# IOT_GRN_MAIN_V1_0_A_-_ESP32.net
KiCad netlist of a schematic drawn in Altium Designer
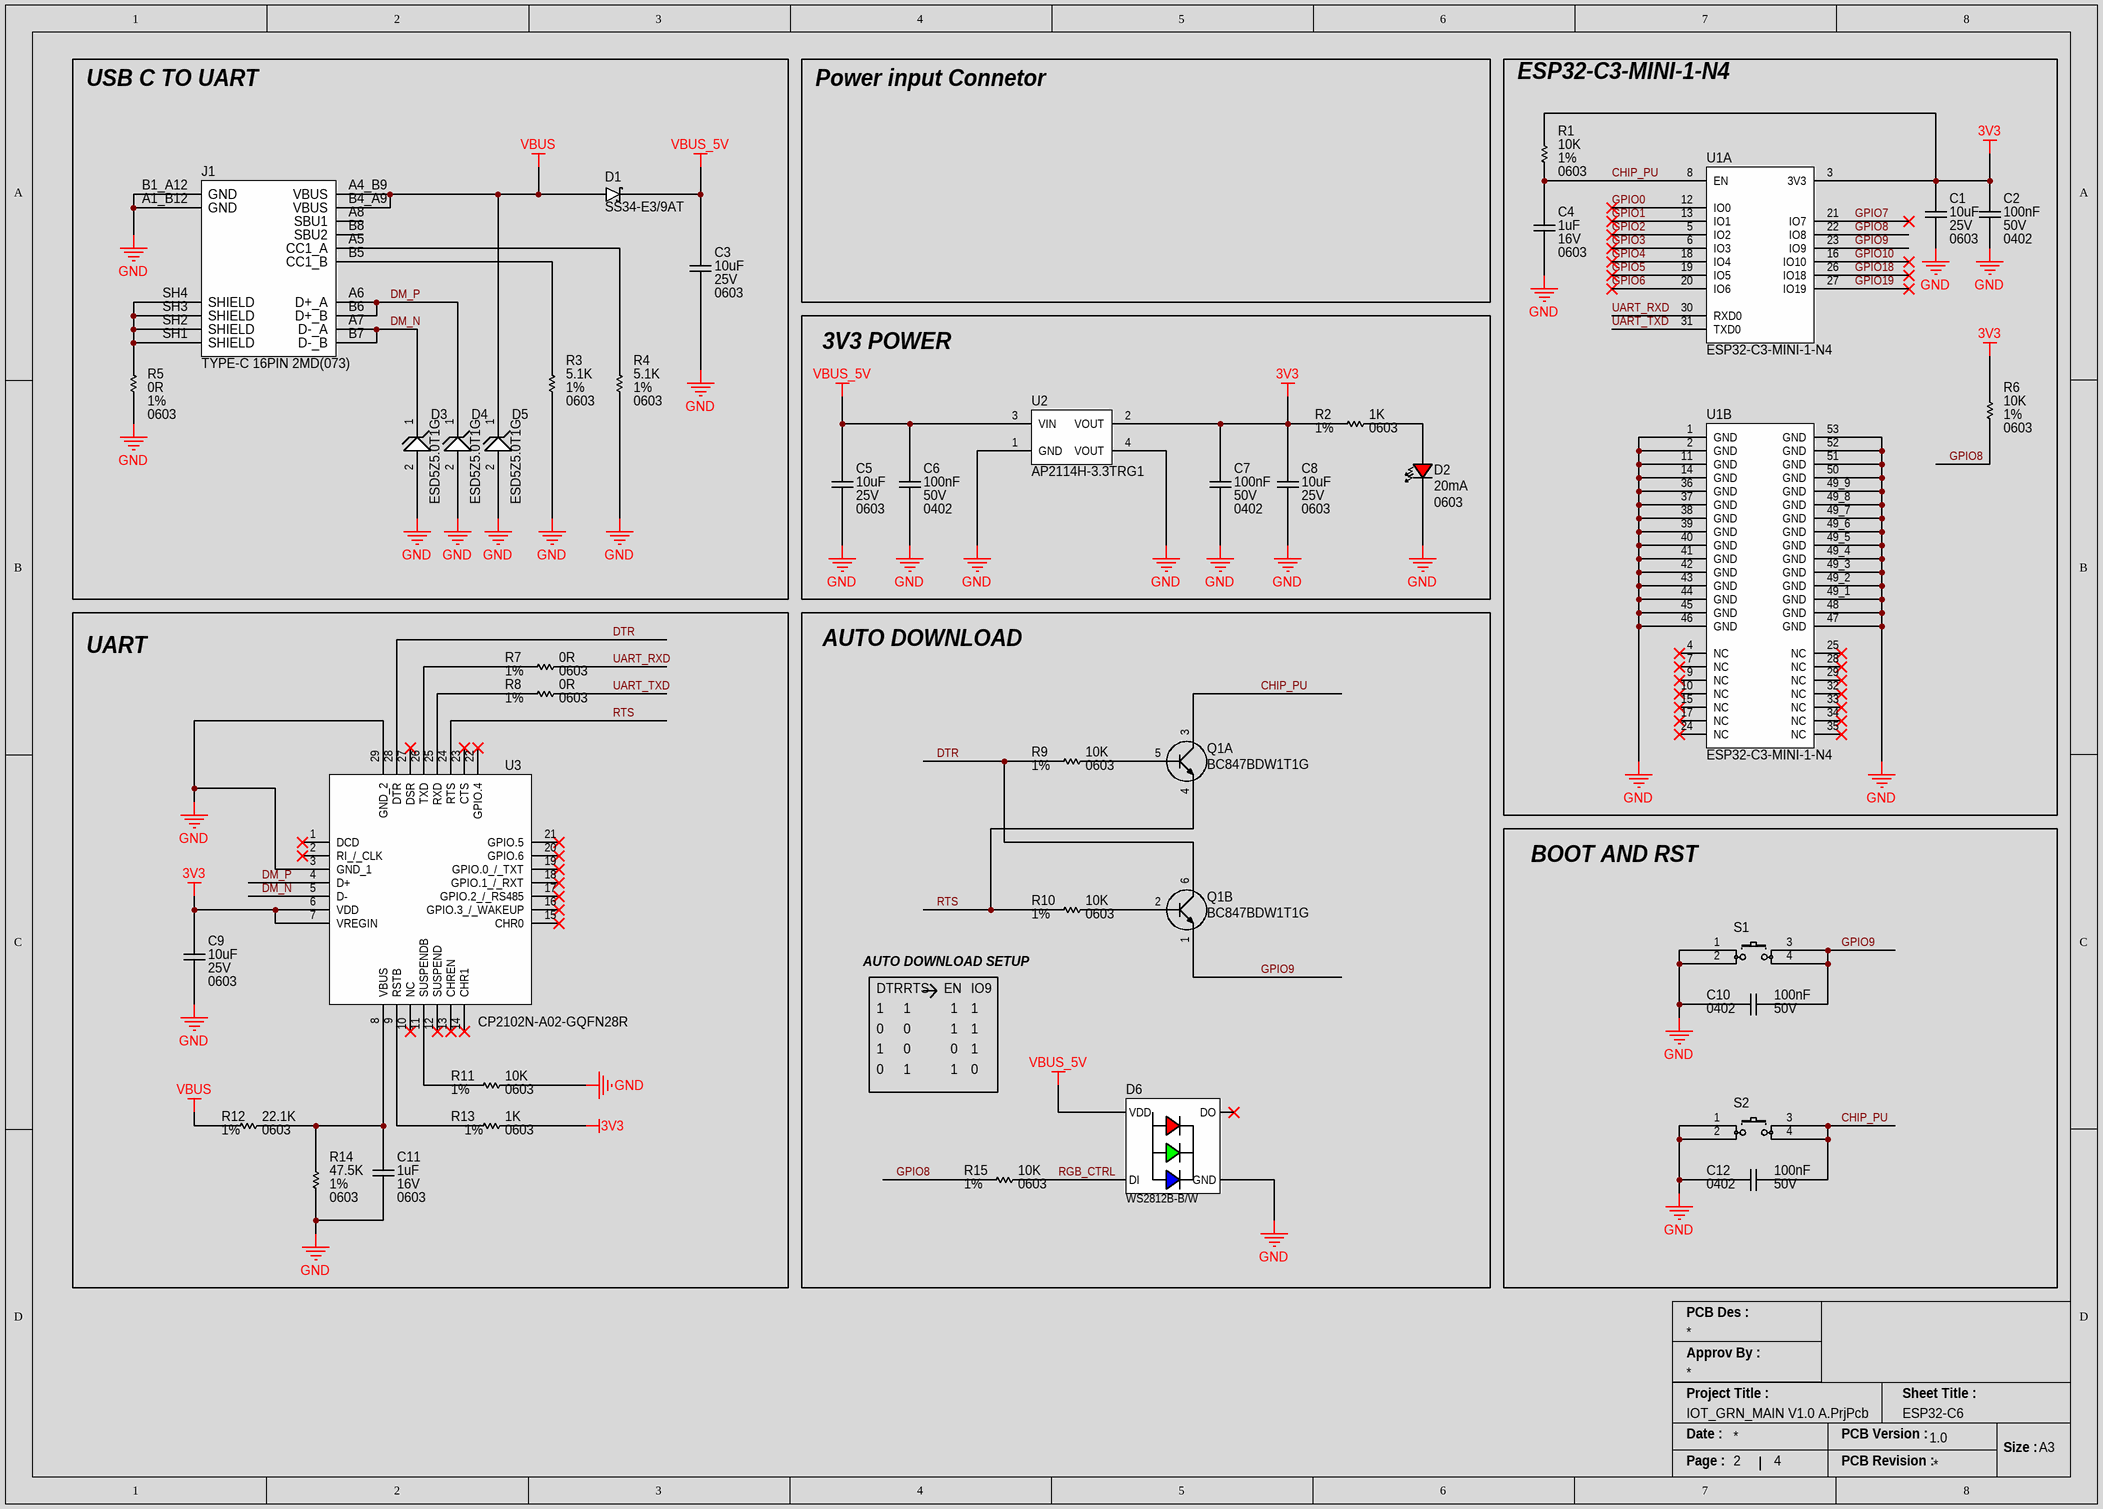
[diagram p0: IOT_GRN_MAIN V1.0 A - ESP32.SchDoc]

(export (version "E")
  (design (tool "Eeschema 10.0.6"))
  (components
    (comp (ref "C1")
      (value "GRM188R61E106MA73D")
      (footprint "CAP_0603_CAPC1608X08N")
      (description "Multilayer Ceramic Capacitor, 10 uF, 25 V, ± 20%, X5R, 0603 [1608 Metric]")
      (fields
        (field (name "MANUFACTURER") "Murata")
        (field (name "TOLERANCE") "20%")
        (field (name "CASE/PACKAGE") "0603")
        (field (name "CAPACITANCE") "10uF")
        (field (name "VOLTAGE RATING") "25V")
      )
      (libsource (lib "Electronic Devices_LIB") (part "CAP_10UF_25V_X5R_0603"))
    )
    (comp (ref "C2")
      (value "GRM155R71H104KE14D")
      (footprint "CAP_0402_CAPC1005X05N")
      (description "Multilayer Ceramic Capacitor, 0.1 uF, 16 V, ± 10%, X7R, 0402 [1005 Metric]")
      (fields
        (field (name "MANUFACTURER") "Murata")
        (field (name "TOLERANCE") "10%")
        (field (name "VOLTAGE RATING") "50V")
        (field (name "CAPACITANCE") "100nF")
        (field (name "CASE/PACKAGE") "0402")
      )
      (libsource (lib "Electronic Devices_LIB") (part "CAP_100NF_50V_X7R_0402"))
    )
    (comp (ref "C3")
      (value "GRM188R61E106MA73D")
      (footprint "CAP_0603_CAPC1608X08N")
      (description "Multilayer Ceramic Capacitor, 10 uF, 25 V, ± 20%, X5R, 0603 [1608 Metric]")
      (fields
        (field (name "MANUFACTURER") "Murata")
        (field (name "TOLERANCE") "20%")
        (field (name "CASE/PACKAGE") "0603")
        (field (name "CAPACITANCE") "10uF")
        (field (name "VOLTAGE RATING") "25V")
      )
      (libsource (lib "Electronic Devices_LIB") (part "CAP_10UF_25V_X5R_0603"))
    )
    (comp (ref "C4")
      (value "CL10A105KO8NNNC")
      (footprint "CAP_0603_CAPC1608X08N")
      (description "CAP CER 1UF 16V X5R 0603")
      (fields
        (field (name "MANUFACTURER") "Samsung")
        (field (name "TOLERANCE") "10%")
        (field (name "VOLTAGE RATING") "16V")
        (field (name "CAPACITANCE") "1uF")
        (field (name "CASE/PACKAGE") "0603")
      )
      (libsource (lib "Electronic Devices_LIB") (part "CAP_1UF_16V_X5R_0603"))
    )
    (comp (ref "C5")
      (value "GRM188R61E106MA73D")
      (footprint "CAP_0603_CAPC1608X08N")
      (description "Multilayer Ceramic Capacitor, 10 uF, 25 V, ± 20%, X5R, 0603 [1608 Metric]")
      (fields
        (field (name "MANUFACTURER") "Murata")
        (field (name "TOLERANCE") "20%")
        (field (name "CASE/PACKAGE") "0603")
        (field (name "CAPACITANCE") "10uF")
        (field (name "VOLTAGE RATING") "25V")
      )
      (libsource (lib "Electronic Devices_LIB") (part "CAP_10UF_25V_X5R_0603"))
    )
    (comp (ref "C6")
      (value "GRM155R71H104KE14D")
      (footprint "CAP_0402_CAPC1005X05N")
      (description "Multilayer Ceramic Capacitor, 0.1 uF, 16 V, ± 10%, X7R, 0402 [1005 Metric]")
      (fields
        (field (name "MANUFACTURER") "Murata")
        (field (name "TOLERANCE") "10%")
        (field (name "VOLTAGE RATING") "50V")
        (field (name "CAPACITANCE") "100nF")
        (field (name "CASE/PACKAGE") "0402")
      )
      (libsource (lib "Electronic Devices_LIB") (part "CAP_100NF_50V_X7R_0402"))
    )
    (comp (ref "C7")
      (value "GRM155R71H104KE14D")
      (footprint "CAP_0402_CAPC1005X05N")
      (description "Multilayer Ceramic Capacitor, 0.1 uF, 16 V, ± 10%, X7R, 0402 [1005 Metric]")
      (fields
        (field (name "MANUFACTURER") "Murata")
        (field (name "TOLERANCE") "10%")
        (field (name "VOLTAGE RATING") "50V")
        (field (name "CAPACITANCE") "100nF")
        (field (name "CASE/PACKAGE") "0402")
      )
      (libsource (lib "Electronic Devices_LIB") (part "CAP_100NF_50V_X7R_0402"))
    )
    (comp (ref "C8")
      (value "GRM188R61E106MA73D")
      (footprint "CAP_0603_CAPC1608X08N")
      (description "Multilayer Ceramic Capacitor, 10 uF, 25 V, ± 20%, X5R, 0603 [1608 Metric]")
      (fields
        (field (name "MANUFACTURER") "Murata")
        (field (name "TOLERANCE") "20%")
        (field (name "CASE/PACKAGE") "0603")
        (field (name "CAPACITANCE") "10uF")
        (field (name "VOLTAGE RATING") "25V")
      )
      (libsource (lib "Electronic Devices_LIB") (part "CAP_10UF_25V_X5R_0603"))
    )
    (comp (ref "C9")
      (value "GRM188R61E106MA73D")
      (footprint "CAP_0603_CAPC1608X08N")
      (description "Multilayer Ceramic Capacitor, 10 uF, 25 V, ± 20%, X5R, 0603 [1608 Metric]")
      (fields
        (field (name "MANUFACTURER") "Murata")
        (field (name "TOLERANCE") "20%")
        (field (name "CASE/PACKAGE") "0603")
        (field (name "CAPACITANCE") "10uF")
        (field (name "VOLTAGE RATING") "25V")
      )
      (libsource (lib "Electronic Devices_LIB") (part "CAP_10UF_25V_X5R_0603"))
    )
    (comp (ref "C10")
      (value "GRM155R71H104KE14D")
      (footprint "CAP_0402_CAPC1005X05N")
      (description "Multilayer Ceramic Capacitor, 0.1 uF, 16 V, ± 10%, X7R, 0402 [1005 Metric]")
      (fields
        (field (name "MANUFACTURER") "Murata")
        (field (name "TOLERANCE") "10%")
        (field (name "VOLTAGE RATING") "50V")
        (field (name "CAPACITANCE") "100nF")
        (field (name "CASE/PACKAGE") "0402")
      )
      (libsource (lib "Electronic Devices_LIB") (part "CAP_100NF_50V_X7R_0402"))
    )
    (comp (ref "C11")
      (value "CL10A105KO8NNNC")
      (footprint "CAP_0603_CAPC1608X08N")
      (description "CAP CER 1UF 16V X5R 0603")
      (fields
        (field (name "MANUFACTURER") "Samsung")
        (field (name "TOLERANCE") "10%")
        (field (name "VOLTAGE RATING") "16V")
        (field (name "CAPACITANCE") "1uF")
        (field (name "CASE/PACKAGE") "0603")
      )
      (libsource (lib "Electronic Devices_LIB") (part "CAP_1UF_16V_X5R_0603"))
    )
    (comp (ref "C12")
      (value "GRM155R71H104KE14D")
      (footprint "CAP_0402_CAPC1005X05N")
      (description "Multilayer Ceramic Capacitor, 0.1 uF, 16 V, ± 10%, X7R, 0402 [1005 Metric]")
      (fields
        (field (name "MANUFACTURER") "Murata")
        (field (name "TOLERANCE") "10%")
        (field (name "VOLTAGE RATING") "50V")
        (field (name "CAPACITANCE") "100nF")
        (field (name "CASE/PACKAGE") "0402")
      )
      (libsource (lib "Electronic Devices_LIB") (part "CAP_100NF_50V_X7R_0402"))
    )
    (comp (ref "D1")
      (value "SS34-E3/9AT")
      (footprint "DIO_Vishay_SMC_MFG")
      (description "Rectifier Diode, schottky, 40V V(Rrm), do-214Ab / Smc")
      (fields (field (name "MANUFACTURER") "Vishay Semiconductors"))
      (libsource (lib "Electronic Devices_LIB") (part "DIO_SCTKY_40V_3A"))
    )
    (comp (ref "D2")
      (value "LTST-C190KRKT")
      (footprint "LED_0603-RED-0.75mm")
      (description "LED,  LTST-C190KRKT")
      (fields
        (field (name "MANUFACTURER") "Vishay Lite-On")
        (field (name "TEST CURRENT") "20mA")
        (field (name "CASE/PACKAGE") "0603")
      )
      (libsource (lib "Electronic Devices_LIB") (part "LED_DIO_RED_20mA_0603"))
    )
    (comp (ref "D3")
      (value "ESD5Z5.0T1G")
      (footprint "SOD523_SODFL1608X70N")
      (description "ESD5Z Series 6.2 V 80 pF 5 Vrwm TVS and ESD Protection Diodes - SOD-523")
      (fields (field (name "MANUFACTURER") "ON Semiconductor"))
      (libsource (lib "Electronic Devices_LIB") (part "DIO_TVS_5V_ESD5Z5.0T1G"))
    )
    (comp (ref "D4")
      (value "ESD5Z5.0T1G")
      (footprint "SOD523_SODFL1608X70N")
      (description "ESD5Z Series 6.2 V 80 pF 5 Vrwm TVS and ESD Protection Diodes - SOD-523")
      (fields (field (name "MANUFACTURER") "ON Semiconductor"))
      (libsource (lib "Electronic Devices_LIB") (part "DIO_TVS_5V_ESD5Z5.0T1G"))
    )
    (comp (ref "D5")
      (value "ESD5Z5.0T1G")
      (footprint "SOD523_SODFL1608X70N")
      (description "ESD5Z Series 6.2 V 80 pF 5 Vrwm TVS and ESD Protection Diodes - SOD-523")
      (fields (field (name "MANUFACTURER") "ON Semiconductor"))
      (libsource (lib "Electronic Devices_LIB") (part "DIO_TVS_5V_ESD5Z5.0T1G"))
    )
    (comp (ref "D6")
      (value "WS2812B-B/W")
      (footprint "LED_RGB_3528_ XL-3528RGBW-WS2812B")
      (description "-25℃~+80℃ Positive post RGB 120° SMD3528-4P Light Emitting Diodes (LED) ROHS")
      (fields (field (name "MANUFACTURER") "XINGLIGHT") (field (name "MANUFACTURER PART NUMBER") "3528"))
      (libsource (lib "Electronic Devices_LIB") (part "LED_DIO_RGB_XL-3528RGBW-WS2812B"))
    )
    (comp (ref "J1")
      (value "TYPE-C 16PIN 2MD(073)")
      (footprint "CONN_USB_C_16P")
      (description "5A 1 Surface Mount 16P Female -25℃~+85℃ Type-C SMD USB Connectors ROHS")
      (fields (field (name "MANUFACTURER") "SHOU HAN"))
      (libsource (lib "Electronic Devices_LIB") (part "CONN_USB_TYPEC_2.0_16P_TYPE-C 16PIN 2MD(073)"))
    )
    (comp (ref "Q1")
      (value "BC847BDW1T1G")
      (footprint "TRANS_BJT_SOT65P210X110-6N")
      (description "ON Semi BC847BDW1T1G Dual NPN Bipolar Transistor; 0.1 A; 45 V; 6-Pin SC-88")
      (fields (field (name "MANUFACTURER") "ON Semiconductor"))
      (libsource (lib "Electronic Devices_LIB") (part "TRANS_BIPOLAR_NPN_BC847BDW1T1G"))
    )
    (comp (ref "R1")
      (value "AC0603FR-1010KL")
      (footprint "RES_0603_RESC1608X04N")
      (description "Chip Resistor Automotive Grade Thick Film 0603 10kOhm 1% Paper T/R")
      (fields
        (field (name "MANUFACTURER") "Yageo")
        (field (name "RESISTANCE") "10K")
        (field (name "TOLERANCE") "1%")
        (field (name "CASE/PACKAGE") "0603")
      )
      (libsource (lib "Electronic Devices_LIB") (part "RES_10K_1%_100mW_0603"))
    )
    (comp (ref "R2")
      (value "AC0603FR-101KL")
      (footprint "RES_0603_RESC1608X04N")
      (description "Chip Resistor Automotive Grade Thick Film 0603 1kOhm 1% Paper T/R")
      (fields
        (field (name "MANUFACTURER") "Yageo")
        (field (name "RESISTANCE") "1K")
        (field (name "TOLERANCE") "1%")
        (field (name "CASE/PACKAGE") "0603")
      )
      (libsource (lib "Electronic Devices_LIB") (part "RES_1K_1%_100mW_0603"))
    )
    (comp (ref "R3")
      (value "RC0603FR-075K1L")
      (footprint "RES_0603_RESC1608X04N")
      (description "SMD Chip Resistor, 5.1 kOhm, ± 1%, 100 mW, 0603 [1608 Metric], Thick Film, General Purpose")
      (fields
        (field (name "MANUFACTURER") "Yageo")
        (field (name "TOLERANCE") "1%")
        (field (name "RESISTANCE") "5.1K")
        (field (name "CASE/PACKAGE") "0603")
      )
      (libsource (lib "Electronic Devices_LIB") (part "RES_5.1K_1%_100mW_0603"))
    )
    (comp (ref "R4")
      (value "RC0603FR-075K1L")
      (footprint "RES_0603_RESC1608X04N")
      (description "SMD Chip Resistor, 5.1 kOhm, ± 1%, 100 mW, 0603 [1608 Metric], Thick Film, General Purpose")
      (fields
        (field (name "MANUFACTURER") "Yageo")
        (field (name "TOLERANCE") "1%")
        (field (name "RESISTANCE") "5.1K")
        (field (name "CASE/PACKAGE") "0603")
      )
      (libsource (lib "Electronic Devices_LIB") (part "RES_5.1K_1%_100mW_0603"))
    )
    (comp (ref "R5")
      (value "RC0603FR-070RL")
      (footprint "RES_0603_RESC1608X04N")
      (description "RC Series 0603 0.1 W 0 Ohm Jumper Surface Mount Thick Film Chip Resistor")
      (fields
        (field (name "MANUFACTURER") "Yageo")
        (field (name "TOLERANCE") "1%")
        (field (name "RESISTANCE") "0R")
        (field (name "CASE CODE (IMPERIAL)") "0603")
      )
      (libsource (lib "Electronic Devices_LIB") (part "RES_0R_1%_100mW_0603"))
    )
    (comp (ref "R6")
      (value "AC0603FR-1010KL")
      (footprint "RES_0603_RESC1608X04N")
      (description "Chip Resistor Automotive Grade Thick Film 0603 10kOhm 1% Paper T/R")
      (fields
        (field (name "MANUFACTURER") "Yageo")
        (field (name "RESISTANCE") "10K")
        (field (name "TOLERANCE") "1%")
        (field (name "CASE/PACKAGE") "0603")
      )
      (libsource (lib "Electronic Devices_LIB") (part "RES_10K_1%_100mW_0603"))
    )
    (comp (ref "R7")
      (value "RC0603FR-070RL")
      (footprint "RES_0603_RESC1608X04N")
      (description "RC Series 0603 0.1 W 0 Ohm Jumper Surface Mount Thick Film Chip Resistor")
      (fields
        (field (name "MANUFACTURER") "Yageo")
        (field (name "TOLERANCE") "1%")
        (field (name "RESISTANCE") "0R")
        (field (name "CASE CODE (IMPERIAL)") "0603")
      )
      (libsource (lib "Electronic Devices_LIB") (part "RES_0R_1%_100mW_0603"))
    )
    (comp (ref "R8")
      (value "RC0603FR-070RL")
      (footprint "RES_0603_RESC1608X04N")
      (description "RC Series 0603 0.1 W 0 Ohm Jumper Surface Mount Thick Film Chip Resistor")
      (fields
        (field (name "MANUFACTURER") "Yageo")
        (field (name "TOLERANCE") "1%")
        (field (name "RESISTANCE") "0R")
        (field (name "CASE CODE (IMPERIAL)") "0603")
      )
      (libsource (lib "Electronic Devices_LIB") (part "RES_0R_1%_100mW_0603"))
    )
    (comp (ref "R9")
      (value "AC0603FR-1010KL")
      (footprint "RES_0603_RESC1608X04N")
      (description "Chip Resistor Automotive Grade Thick Film 0603 10kOhm 1% Paper T/R")
      (fields
        (field (name "MANUFACTURER") "Yageo")
        (field (name "RESISTANCE") "10K")
        (field (name "TOLERANCE") "1%")
        (field (name "CASE/PACKAGE") "0603")
      )
      (libsource (lib "Electronic Devices_LIB") (part "RES_10K_1%_100mW_0603"))
    )
    (comp (ref "R10")
      (value "AC0603FR-1010KL")
      (footprint "RES_0603_RESC1608X04N")
      (description "Chip Resistor Automotive Grade Thick Film 0603 10kOhm 1% Paper T/R")
      (fields
        (field (name "MANUFACTURER") "Yageo")
        (field (name "RESISTANCE") "10K")
        (field (name "TOLERANCE") "1%")
        (field (name "CASE/PACKAGE") "0603")
      )
      (libsource (lib "Electronic Devices_LIB") (part "RES_10K_1%_100mW_0603"))
    )
    (comp (ref "R11")
      (value "AC0603FR-1010KL")
      (footprint "RES_0603_RESC1608X04N")
      (description "Chip Resistor Automotive Grade Thick Film 0603 10kOhm 1% Paper T/R")
      (fields
        (field (name "MANUFACTURER") "Yageo")
        (field (name "RESISTANCE") "10K")
        (field (name "TOLERANCE") "1%")
        (field (name "CASE/PACKAGE") "0603")
      )
      (libsource (lib "Electronic Devices_LIB") (part "RES_10K_1%_100mW_0603"))
    )
    (comp (ref "R12")
      (value "RC0603FR-0722K1L")
      (footprint "RES_0603_RESC1608X04N")
      (description "SMD Chip Resistor, 22.1 kOhm, ± 1%, 100 mW, 0603 [1608 Metric], Thick Film, General Purpose")
      (fields
        (field (name "MANUFACTURER") "Yageo")
        (field (name "RESISTANCE") "22.1K")
        (field (name "TOLERANCE") "1%")
        (field (name "CASE/PACKAGE") "0603")
      )
      (libsource (lib "Electronic Devices_LIB") (part "RES_22.1K_1%_100mW_0603"))
    )
    (comp (ref "R13")
      (value "AC0603FR-101KL")
      (footprint "RES_0603_RESC1608X04N")
      (description "Chip Resistor Automotive Grade Thick Film 0603 1kOhm 1% Paper T/R")
      (fields
        (field (name "MANUFACTURER") "Yageo")
        (field (name "RESISTANCE") "1K")
        (field (name "TOLERANCE") "1%")
        (field (name "CASE/PACKAGE") "0603")
      )
      (libsource (lib "Electronic Devices_LIB") (part "RES_1K_1%_100mW_0603"))
    )
    (comp (ref "R14")
      (value "AC0603FR-0747K5L")
      (footprint "RES_0603_RESC1608X04N")
      (description "SMD Chip Resistor, 47.5 kOhm, ± 1%, 100 mW, 0603 [1608 Metric], Thick Film, General Purpose")
      (fields
        (field (name "MANUFACTURER") "Yageo")
        (field (name "TOLERANCE") "1%")
        (field (name "RESISTANCE") "47.5K")
        (field (name "CASE/PACKAGE") "0603")
      )
      (libsource (lib "Electronic Devices_LIB") (part "RES_47.5K_1%_100mW_0603"))
    )
    (comp (ref "R15")
      (value "AC0603FR-1010KL")
      (footprint "RES_0603_RESC1608X04N")
      (description "Chip Resistor Automotive Grade Thick Film 0603 10kOhm 1% Paper T/R")
      (fields
        (field (name "MANUFACTURER") "Yageo")
        (field (name "RESISTANCE") "10K")
        (field (name "TOLERANCE") "1%")
        (field (name "CASE/PACKAGE") "0603")
      )
      (libsource (lib "Electronic Devices_LIB") (part "RES_10K_1%_100mW_0603"))
    )
    (comp (ref "S1")
      (value "PTS526SK15SMTR2LFS")
      (footprint "SWT_NO_PTS526SK15SMTR2LFS")
      (description "Switch Tactile N.O. SPST Round Button Gull Wing 0.05A 12VDC 200000Cycles 2.55N SMD T/R")
      (fields (field (name "MANUFACTURER") "ITT C&K"))
      (libsource (lib "Electronic Devices_LIB") (part "SWITCH_NO_SPST_0.05A"))
    )
    (comp (ref "S2")
      (value "PTS526SK15SMTR2LFS")
      (footprint "SWT_NO_PTS526SK15SMTR2LFS")
      (description "Switch Tactile N.O. SPST Round Button Gull Wing 0.05A 12VDC 200000Cycles 2.55N SMD T/R")
      (fields (field (name "MANUFACTURER") "ITT C&K"))
      (libsource (lib "Electronic Devices_LIB") (part "SWITCH_NO_SPST_0.05A"))
    )
    (comp (ref "U1")
      (value "ESP32-C3-MINI-1-N4")
      (footprint "XCVR_ESP32-C3-MINI-1-N4")
      (description "Multiprotocol Modules SMD module, ESP32-C3FN4, PCB antenna, -40 C +85 C")
      (fields (field (name "MANUFACTURER") "Espressif Systems"))
      (libsource (lib "Electronic Devices_LIB") (part "IC_MODULE_ESP32-C3-MINI-1-N4"))
    )
    (comp (ref "U2")
      (value "AP2114H-3.3TRG1")
      (footprint "IC_REG_SOT230P700X180-4N")
      (description "IC REG LDO 3.3V 1A SOT223")
      (fields (field (name "MANUFACTURER") "Diodes"))
      (libsource (lib "Electronic Devices_LIB") (part "IC_REG_LDO_3.3V_1A_AP2114H-3.3TRG1"))
    )
    (comp (ref "U3")
      (value "CP2102N-A02-GQFN28R")
      (footprint "IC_BRIDGE_UART_QFN50P500X500X80-29N-D")
      (description "Full Speed USB to UART Bridge USB 2.0 3.3V T/R Automotive 28-Pin QFN EP")
      (fields (field (name "MANUFACTURER") "Silicon Labs"))
      (libsource (lib "Electronic Devices_LIB") (part "IC_BRIDGE_UART_CP2102N-A02-GQFN28R"))
    )
  )
  (nets
    (net (code "1") (name "/CHIP_PU") (class "Default")
      (node (ref "C12") (pin "1") (pinfunction "1_1") (pintype "passive"))
      (node (ref "C4") (pin "2") (pinfunction "2_2") (pintype "passive"))
      (node (ref "Q1") (pin "3") (pinfunction "COLLECTOR_1_3") (pintype "passive"))
      (node (ref "R1") (pin "2") (pinfunction "2_2") (pintype "passive"))
      (node (ref "S2") (pin "3") (pinfunction "NO1_3") (pintype "passive"))
      (node (ref "S2") (pin "4") (pinfunction "NO2_4") (pintype "passive"))
      (node (ref "U1") (pin "8") (pinfunction "EN_8") (pintype "passive"))
    )
    (net (code "2") (name "/DM_N") (class "Default")
      (node (ref "D3") (pin "1") (pinfunction "K_1") (pintype "passive"))
      (node (ref "J1") (pin "A7") (pinfunction "D-_A_A7") (pintype "passive"))
      (node (ref "J1") (pin "B7") (pinfunction "D-_B_B7") (pintype "passive"))
      (node (ref "U3") (pin "5") (pinfunction "D-_5") (pintype "passive"))
    )
    (net (code "3") (name "/DM_P") (class "Default")
      (node (ref "D4") (pin "1") (pinfunction "K_1") (pintype "passive"))
      (node (ref "J1") (pin "A6") (pinfunction "D+_A_A6") (pintype "passive"))
      (node (ref "J1") (pin "B6") (pinfunction "D+_B_B6") (pintype "passive"))
      (node (ref "U3") (pin "4") (pinfunction "D+_4") (pintype "passive"))
    )
    (net (code "4") (name "/DTR") (class "Default")
      (node (ref "Q1") (pin "6") (pinfunction "COLLECTOR_2_6") (pintype "passive"))
      (node (ref "R9") (pin "2") (pinfunction "2_2") (pintype "passive"))
      (node (ref "U3") (pin "28") (pinfunction "DTR_28") (pintype "passive"))
    )
    (net (code "5") (name "/GPIO0") (class "Default")
      (node (ref "U1") (pin "12") (pinfunction "IO0_12") (pintype "passive+no_connect"))
    )
    (net (code "6") (name "/GPIO1") (class "Default")
      (node (ref "U1") (pin "13") (pinfunction "IO1_13") (pintype "passive+no_connect"))
    )
    (net (code "7") (name "/GPIO2") (class "Default")
      (node (ref "U1") (pin "5") (pinfunction "IO2_5") (pintype "passive+no_connect"))
    )
    (net (code "8") (name "/GPIO3") (class "Default")
      (node (ref "U1") (pin "6") (pinfunction "IO3_6") (pintype "passive+no_connect"))
    )
    (net (code "9") (name "/GPIO4") (class "Default")
      (node (ref "U1") (pin "18") (pinfunction "IO4_18") (pintype "passive+no_connect"))
    )
    (net (code "10") (name "/GPIO5") (class "Default")
      (node (ref "U1") (pin "19") (pinfunction "IO5_19") (pintype "passive+no_connect"))
    )
    (net (code "11") (name "/GPIO6") (class "Default")
      (node (ref "U1") (pin "20") (pinfunction "IO6_20") (pintype "passive+no_connect"))
    )
    (net (code "12") (name "/GPIO7") (class "Default")
      (node (ref "U1") (pin "21") (pinfunction "IO7_21") (pintype "passive+no_connect"))
    )
    (net (code "13") (name "/GPIO8") (class "Default")
      (node (ref "R15") (pin "2") (pinfunction "2_2") (pintype "passive"))
      (node (ref "R6") (pin "2") (pinfunction "2_2") (pintype "passive"))
      (node (ref "U1") (pin "22") (pinfunction "IO8_22") (pintype "passive"))
    )
    (net (code "14") (name "/GPIO9") (class "Default")
      (node (ref "C10") (pin "1") (pinfunction "1_1") (pintype "passive"))
      (node (ref "Q1") (pin "1") (pinfunction "EMITTER_2_1") (pintype "passive"))
      (node (ref "S1") (pin "3") (pinfunction "NO1_3") (pintype "passive"))
      (node (ref "S1") (pin "4") (pinfunction "NO2_4") (pintype "passive"))
      (node (ref "U1") (pin "23") (pinfunction "IO9_23") (pintype "passive"))
    )
    (net (code "15") (name "/GPIO10") (class "Default")
      (node (ref "U1") (pin "16") (pinfunction "IO10_16") (pintype "passive+no_connect"))
    )
    (net (code "16") (name "/GPIO18") (class "Default")
      (node (ref "U1") (pin "26") (pinfunction "IO18_26") (pintype "passive+no_connect"))
    )
    (net (code "17") (name "/GPIO19") (class "Default")
      (node (ref "U1") (pin "27") (pinfunction "IO19_27") (pintype "passive+no_connect"))
    )
    (net (code "18") (name "/RGB_CTRL") (class "Default")
      (node (ref "D6") (pin "2") (pinfunction "DI_2") (pintype "passive"))
      (node (ref "R15") (pin "1") (pinfunction "1_1") (pintype "passive"))
    )
    (net (code "19") (name "/RTS") (class "Default")
      (node (ref "Q1") (pin "4") (pinfunction "EMITTER_1_4") (pintype "passive"))
      (node (ref "R10") (pin "2") (pinfunction "2_2") (pintype "passive"))
      (node (ref "U3") (pin "24") (pinfunction "RTS_24") (pintype "passive"))
    )
    (net (code "20") (name "/UART_RXD") (class "Default")
      (node (ref "R7") (pin "1") (pinfunction "1_1") (pintype "passive"))
      (node (ref "U1") (pin "30") (pinfunction "RXD0_30") (pintype "passive"))
    )
    (net (code "21") (name "/UART_TXD") (class "Default")
      (node (ref "R8") (pin "1") (pinfunction "1_1") (pintype "passive"))
      (node (ref "U1") (pin "31") (pinfunction "TXD0_31") (pintype "passive"))
    )
    (net (code "22") (name "3V3") (class "Default")
      (node (ref "C1") (pin "2") (pinfunction "2_2") (pintype "passive"))
      (node (ref "C2") (pin "2") (pinfunction "2_2") (pintype "passive"))
      (node (ref "C7") (pin "2") (pinfunction "2_2") (pintype "passive"))
      (node (ref "C8") (pin "2") (pinfunction "2_2") (pintype "passive"))
      (node (ref "C9") (pin "2") (pinfunction "2_2") (pintype "passive"))
      (node (ref "R1") (pin "1") (pinfunction "1_1") (pintype "passive"))
      (node (ref "R13") (pin "2") (pinfunction "2_2") (pintype "passive"))
      (node (ref "R2") (pin "1") (pinfunction "1_1") (pintype "passive"))
      (node (ref "R6") (pin "1") (pinfunction "1_1") (pintype "passive"))
      (node (ref "U1") (pin "3") (pinfunction "3V3_3") (pintype "passive"))
      (node (ref "U2") (pin "2") (pinfunction "VOUT_2") (pintype "passive"))
      (node (ref "U3") (pin "6") (pinfunction "VDD_6") (pintype "passive"))
      (node (ref "U3") (pin "7") (pinfunction "VREGIN_7") (pintype "passive"))
    )
    (net (code "23") (name "GND") (class "Default")
      (node (ref "C1") (pin "1") (pinfunction "1_1") (pintype "passive"))
      (node (ref "C10") (pin "2") (pinfunction "2_2") (pintype "passive"))
      (node (ref "C11") (pin "1") (pinfunction "1_1") (pintype "passive"))
      (node (ref "C12") (pin "2") (pinfunction "2_2") (pintype "passive"))
      (node (ref "C2") (pin "1") (pinfunction "1_1") (pintype "passive"))
      (node (ref "C3") (pin "1") (pinfunction "1_1") (pintype "passive"))
      (node (ref "C4") (pin "1") (pinfunction "1_1") (pintype "passive"))
      (node (ref "C5") (pin "1") (pinfunction "1_1") (pintype "passive"))
      (node (ref "C6") (pin "1") (pinfunction "1_1") (pintype "passive"))
      (node (ref "C7") (pin "1") (pinfunction "1_1") (pintype "passive"))
      (node (ref "C8") (pin "1") (pinfunction "1_1") (pintype "passive"))
      (node (ref "C9") (pin "1") (pinfunction "1_1") (pintype "passive"))
      (node (ref "D2") (pin "1") (pinfunction "C_1") (pintype "passive"))
      (node (ref "D3") (pin "2") (pinfunction "A_2") (pintype "passive"))
      (node (ref "D4") (pin "2") (pinfunction "A_2") (pintype "passive"))
      (node (ref "D5") (pin "2") (pinfunction "A_2") (pintype "passive"))
      (node (ref "D6") (pin "1") (pinfunction "GND_1") (pintype "power_in"))
      (node (ref "J1") (pin "A1_B12") (pinfunction "GND_A1_B12") (pintype "power_in"))
      (node (ref "J1") (pin "B1_A12") (pinfunction "GND_B1_A12") (pintype "power_in"))
      (node (ref "R11") (pin "2") (pinfunction "2_2") (pintype "passive"))
      (node (ref "R14") (pin "1") (pinfunction "1_1") (pintype "passive"))
      (node (ref "R3") (pin "1") (pinfunction "1_1") (pintype "passive"))
      (node (ref "R4") (pin "1") (pinfunction "1_1") (pintype "passive"))
      (node (ref "R5") (pin "1") (pinfunction "1_1") (pintype "passive"))
      (node (ref "S1") (pin "1") (pinfunction "COM_1_1") (pintype "passive"))
      (node (ref "S1") (pin "2") (pinfunction "COM2_2") (pintype "passive"))
      (node (ref "S2") (pin "1") (pinfunction "COM_1_1") (pintype "passive"))
      (node (ref "S2") (pin "2") (pinfunction "COM2_2") (pintype "passive"))
      (node (ref "U1") (pin "1") (pinfunction "GND_1") (pintype "power_in"))
      (node (ref "U1") (pin "11") (pinfunction "GND_11") (pintype "power_in"))
      (node (ref "U1") (pin "14") (pinfunction "GND_14") (pintype "power_in"))
      (node (ref "U1") (pin "2") (pinfunction "GND_2") (pintype "power_in"))
      (node (ref "U1") (pin "36") (pinfunction "GND_36") (pintype "power_in"))
      (node (ref "U1") (pin "37") (pinfunction "GND_37") (pintype "power_in"))
      (node (ref "U1") (pin "38") (pinfunction "GND_38") (pintype "power_in"))
      (node (ref "U1") (pin "39") (pinfunction "GND_39") (pintype "power_in"))
      (node (ref "U1") (pin "40") (pinfunction "GND_40") (pintype "power_in"))
      (node (ref "U1") (pin "41") (pinfunction "GND_41") (pintype "power_in"))
      (node (ref "U1") (pin "42") (pinfunction "GND_42") (pintype "power_in"))
      (node (ref "U1") (pin "43") (pinfunction "GND_43") (pintype "power_in"))
      (node (ref "U1") (pin "44") (pinfunction "GND_44") (pintype "power_in"))
      (node (ref "U1") (pin "45") (pinfunction "GND_45") (pintype "power_in"))
      (node (ref "U1") (pin "46") (pinfunction "GND_46") (pintype "power_in"))
      (node (ref "U1") (pin "47") (pinfunction "GND_47") (pintype "power_in"))
      (node (ref "U1") (pin "48") (pinfunction "GND_48") (pintype "power_in"))
      (node (ref "U1") (pin "49_1") (pinfunction "GND_49_1") (pintype "power_in"))
      (node (ref "U1") (pin "49_2") (pinfunction "GND_49_2") (pintype "power_in"))
      (node (ref "U1") (pin "49_3") (pinfunction "GND_49_3") (pintype "power_in"))
      (node (ref "U1") (pin "49_4") (pinfunction "GND_49_4") (pintype "power_in"))
      (node (ref "U1") (pin "49_5") (pinfunction "GND_49_5") (pintype "power_in"))
      (node (ref "U1") (pin "49_6") (pinfunction "GND_49_6") (pintype "power_in"))
      (node (ref "U1") (pin "49_7") (pinfunction "GND_49_7") (pintype "power_in"))
      (node (ref "U1") (pin "49_8") (pinfunction "GND_49_8") (pintype "power_in"))
      (node (ref "U1") (pin "49_9") (pinfunction "GND_49_9") (pintype "power_in"))
      (node (ref "U1") (pin "50") (pinfunction "GND_50") (pintype "power_in"))
      (node (ref "U1") (pin "51") (pinfunction "GND_51") (pintype "power_in"))
      (node (ref "U1") (pin "52") (pinfunction "GND_52") (pintype "power_in"))
      (node (ref "U1") (pin "53") (pinfunction "GND_53") (pintype "power_in"))
      (node (ref "U2") (pin "1") (pinfunction "GND_1") (pintype "passive"))
      (node (ref "U2") (pin "4") (pinfunction "VOUT_4") (pintype "passive"))
      (node (ref "U3") (pin "29") (pinfunction "GND_2_29") (pintype "passive"))
      (node (ref "U3") (pin "3") (pinfunction "GND_1_3") (pintype "passive"))
    )
    (net (code "24") (name "Net-(D2-A)") (class "Default")
      (node (ref "D2") (pin "2") (pinfunction "A_2") (pintype "passive"))
      (node (ref "R2") (pin "2") (pinfunction "2_2") (pintype "passive"))
    )
    (net (code "25") (name "Net-(J1-CC1_A)") (class "Default")
      (node (ref "J1") (pin "A5") (pinfunction "CC1_A_A5") (pintype "passive"))
      (node (ref "R4") (pin "2") (pinfunction "2_2") (pintype "passive"))
    )
    (net (code "26") (name "Net-(J1-CC1_B)") (class "Default")
      (node (ref "J1") (pin "B5") (pinfunction "CC1_B_B5") (pintype "passive"))
      (node (ref "R3") (pin "2") (pinfunction "2_2") (pintype "passive"))
    )
    (net (code "27") (name "Net-(J1-SHIELD-PadSH1)") (class "Default")
      (node (ref "J1") (pin "SH1") (pinfunction "SHIELD_SH1") (pintype "passive"))
      (node (ref "J1") (pin "SH2") (pinfunction "SHIELD_SH2") (pintype "passive"))
      (node (ref "J1") (pin "SH3") (pinfunction "SHIELD_SH3") (pintype "passive"))
      (node (ref "J1") (pin "SH4") (pinfunction "SHIELD_SH4") (pintype "passive"))
      (node (ref "R5") (pin "2") (pinfunction "2_2") (pintype "passive"))
    )
    (net (code "28") (name "Net-(Q1A-BASE_1)") (class "Default")
      (node (ref "Q1") (pin "5") (pinfunction "BASE_1_5") (pintype "passive"))
      (node (ref "R9") (pin "1") (pinfunction "1_1") (pintype "passive"))
    )
    (net (code "29") (name "Net-(Q1B-BASE_2)") (class "Default")
      (node (ref "Q1") (pin "2") (pinfunction "BASE_2_2") (pintype "passive"))
      (node (ref "R10") (pin "1") (pinfunction "1_1") (pintype "passive"))
    )
    (net (code "30") (name "Net-(U3-RSTB)") (class "Default")
      (node (ref "R13") (pin "1") (pinfunction "1_1") (pintype "passive"))
      (node (ref "U3") (pin "9") (pinfunction "RSTB_9") (pintype "passive"))
    )
    (net (code "31") (name "Net-(U3-RXD)") (class "Default")
      (node (ref "R8") (pin "2") (pinfunction "2_2") (pintype "passive"))
      (node (ref "U3") (pin "25") (pinfunction "RXD_25") (pintype "passive"))
    )
    (net (code "32") (name "Net-(U3-SUSPENDB)") (class "Default")
      (node (ref "R11") (pin "1") (pinfunction "1_1") (pintype "passive"))
      (node (ref "U3") (pin "11") (pinfunction "SUSPENDB_11") (pintype "passive"))
    )
    (net (code "33") (name "Net-(U3-TXD)") (class "Default")
      (node (ref "R7") (pin "2") (pinfunction "2_2") (pintype "passive"))
      (node (ref "U3") (pin "26") (pinfunction "TXD_26") (pintype "passive"))
    )
    (net (code "34") (name "Net-(U3-VBUS)") (class "Default")
      (node (ref "C11") (pin "2") (pinfunction "2_2") (pintype "passive"))
      (node (ref "R12") (pin "2") (pinfunction "2_2") (pintype "passive"))
      (node (ref "R14") (pin "2") (pinfunction "2_2") (pintype "passive"))
      (node (ref "U3") (pin "8") (pinfunction "VBUS_8") (pintype "passive"))
    )
    (net (code "35") (name "VBUS") (class "Default")
      (node (ref "D1") (pin "2") (pinfunction "A_2") (pintype "passive"))
      (node (ref "D5") (pin "1") (pinfunction "K_1") (pintype "passive"))
      (node (ref "J1") (pin "A4_B9") (pinfunction "VBUS_A4_B9") (pintype "power_in"))
      (node (ref "J1") (pin "B4_A9") (pinfunction "VBUS_B4_A9") (pintype "power_in"))
      (node (ref "R12") (pin "1") (pinfunction "1_1") (pintype "passive"))
    )
    (net (code "36") (name "VBUS_5V") (class "Default")
      (node (ref "C3") (pin "2") (pinfunction "2_2") (pintype "passive"))
      (node (ref "C5") (pin "2") (pinfunction "2_2") (pintype "passive"))
      (node (ref "C6") (pin "2") (pinfunction "2_2") (pintype "passive"))
      (node (ref "D1") (pin "1") (pinfunction "K_1") (pintype "passive"))
      (node (ref "D6") (pin "3") (pinfunction "VDD_3") (pintype "power_in"))
      (node (ref "U2") (pin "3") (pinfunction "VIN_3") (pintype "passive"))
    )
    (net (code "37") (name "unconnected-(D6-DO-Pad4)") (class "Default")
      (node (ref "D6") (pin "4") (pinfunction "DO_4") (pintype "passive+no_connect"))
    )
    (net (code "38") (name "unconnected-(J1-SBU1-PadA8)") (class "Default")
      (node (ref "J1") (pin "A8") (pinfunction "SBU1_A8") (pintype "passive"))
    )
    (net (code "39") (name "unconnected-(J1-SBU2-PadB8)") (class "Default")
      (node (ref "J1") (pin "B8") (pinfunction "SBU2_B8") (pintype "passive"))
    )
    (net (code "40") (name "unconnected-(U1B-NC-Pad4)") (class "Default")
      (node (ref "U1") (pin "4") (pinfunction "NC_4") (pintype "passive+no_connect"))
    )
    (net (code "41") (name "unconnected-(U1B-NC-Pad7)") (class "Default")
      (node (ref "U1") (pin "7") (pinfunction "NC_7") (pintype "passive+no_connect"))
    )
    (net (code "42") (name "unconnected-(U1B-NC-Pad9)") (class "Default")
      (node (ref "U1") (pin "9") (pinfunction "NC_9") (pintype "passive+no_connect"))
    )
    (net (code "43") (name "unconnected-(U1B-NC-Pad10)") (class "Default")
      (node (ref "U1") (pin "10") (pinfunction "NC_10") (pintype "passive+no_connect"))
    )
    (net (code "44") (name "unconnected-(U1B-NC-Pad15)") (class "Default")
      (node (ref "U1") (pin "15") (pinfunction "NC_15") (pintype "passive+no_connect"))
    )
    (net (code "45") (name "unconnected-(U1B-NC-Pad17)") (class "Default")
      (node (ref "U1") (pin "17") (pinfunction "NC_17") (pintype "passive+no_connect"))
    )
    (net (code "46") (name "unconnected-(U1B-NC-Pad24)") (class "Default")
      (node (ref "U1") (pin "24") (pinfunction "NC_24") (pintype "passive+no_connect"))
    )
    (net (code "47") (name "unconnected-(U1B-NC-Pad25)") (class "Default")
      (node (ref "U1") (pin "25") (pinfunction "NC_25") (pintype "passive+no_connect"))
    )
    (net (code "48") (name "unconnected-(U1B-NC-Pad28)") (class "Default")
      (node (ref "U1") (pin "28") (pinfunction "NC_28") (pintype "passive+no_connect"))
    )
    (net (code "49") (name "unconnected-(U1B-NC-Pad29)") (class "Default")
      (node (ref "U1") (pin "29") (pinfunction "NC_29") (pintype "passive+no_connect"))
    )
    (net (code "50") (name "unconnected-(U1B-NC-Pad32)") (class "Default")
      (node (ref "U1") (pin "32") (pinfunction "NC_32") (pintype "passive+no_connect"))
    )
    (net (code "51") (name "unconnected-(U1B-NC-Pad33)") (class "Default")
      (node (ref "U1") (pin "33") (pinfunction "NC_33") (pintype "passive+no_connect"))
    )
    (net (code "52") (name "unconnected-(U1B-NC-Pad34)") (class "Default")
      (node (ref "U1") (pin "34") (pinfunction "NC_34") (pintype "passive+no_connect"))
    )
    (net (code "53") (name "unconnected-(U1B-NC-Pad35)") (class "Default")
      (node (ref "U1") (pin "35") (pinfunction "NC_35") (pintype "passive+no_connect"))
    )
    (net (code "54") (name "unconnected-(U3-CHR0-Pad15)") (class "Default")
      (node (ref "U3") (pin "15") (pinfunction "CHR0_15") (pintype "passive+no_connect"))
    )
    (net (code "55") (name "unconnected-(U3-CHR1-Pad14)") (class "Default")
      (node (ref "U3") (pin "14") (pinfunction "CHR1_14") (pintype "passive+no_connect"))
    )
    (net (code "56") (name "unconnected-(U3-CHREN-Pad13)") (class "Default")
      (node (ref "U3") (pin "13") (pinfunction "CHREN_13") (pintype "passive+no_connect"))
    )
    (net (code "57") (name "unconnected-(U3-CTS-Pad23)") (class "Default")
      (node (ref "U3") (pin "23") (pinfunction "CTS_23") (pintype "passive+no_connect"))
    )
    (net (code "58") (name "unconnected-(U3-DCD-Pad1)") (class "Default")
      (node (ref "U3") (pin "1") (pinfunction "DCD_1") (pintype "passive+no_connect"))
    )
    (net (code "59") (name "unconnected-(U3-DSR-Pad27)") (class "Default")
      (node (ref "U3") (pin "27") (pinfunction "DSR_27") (pintype "passive+no_connect"))
    )
    (net (code "60") (name "unconnected-(U3-GPIO.0_{slash}_TXT-Pad19)") (class "Default")
      (node (ref "U3") (pin "19") (pinfunction "GPIO.0_/_TXT_19") (pintype "passive+no_connect"))
    )
    (net (code "61") (name "unconnected-(U3-GPIO.1_{slash}_RXT-Pad18)") (class "Default")
      (node (ref "U3") (pin "18") (pinfunction "GPIO.1_/_RXT_18") (pintype "passive+no_connect"))
    )
    (net (code "62") (name "unconnected-(U3-GPIO.2_{slash}_RS485-Pad17)") (class "Default")
      (node (ref "U3") (pin "17") (pinfunction "GPIO.2_/_RS485_17") (pintype "passive+no_connect"))
    )
    (net (code "63") (name "unconnected-(U3-GPIO.3_{slash}_WAKEUP-Pad16)") (class "Default")
      (node (ref "U3") (pin "16") (pinfunction "GPIO.3_/_WAKEUP_16") (pintype "passive+no_connect"))
    )
    (net (code "64") (name "unconnected-(U3-GPIO.4-Pad22)") (class "Default")
      (node (ref "U3") (pin "22") (pinfunction "GPIO.4_22") (pintype "passive+no_connect"))
    )
    (net (code "65") (name "unconnected-(U3-GPIO.5-Pad21)") (class "Default")
      (node (ref "U3") (pin "21") (pinfunction "GPIO.5_21") (pintype "passive+no_connect"))
    )
    (net (code "66") (name "unconnected-(U3-GPIO.6-Pad20)") (class "Default")
      (node (ref "U3") (pin "20") (pinfunction "GPIO.6_20") (pintype "passive+no_connect"))
    )
    (net (code "67") (name "unconnected-(U3-NC-Pad10)") (class "Default")
      (node (ref "U3") (pin "10") (pinfunction "NC_10") (pintype "passive+no_connect"))
    )
    (net (code "68") (name "unconnected-(U3-RI_{slash}_CLK-Pad2)") (class "Default")
      (node (ref "U3") (pin "2") (pinfunction "RI_/_CLK_2") (pintype "passive+no_connect"))
    )
    (net (code "69") (name "unconnected-(U3-SUSPEND-Pad12)") (class "Default")
      (node (ref "U3") (pin "12") (pinfunction "SUSPEND_12") (pintype "passive+no_connect"))
    )
  )
)
